# Sheet1.net
KiCad netlist of a schematic drawn in Altium Designer
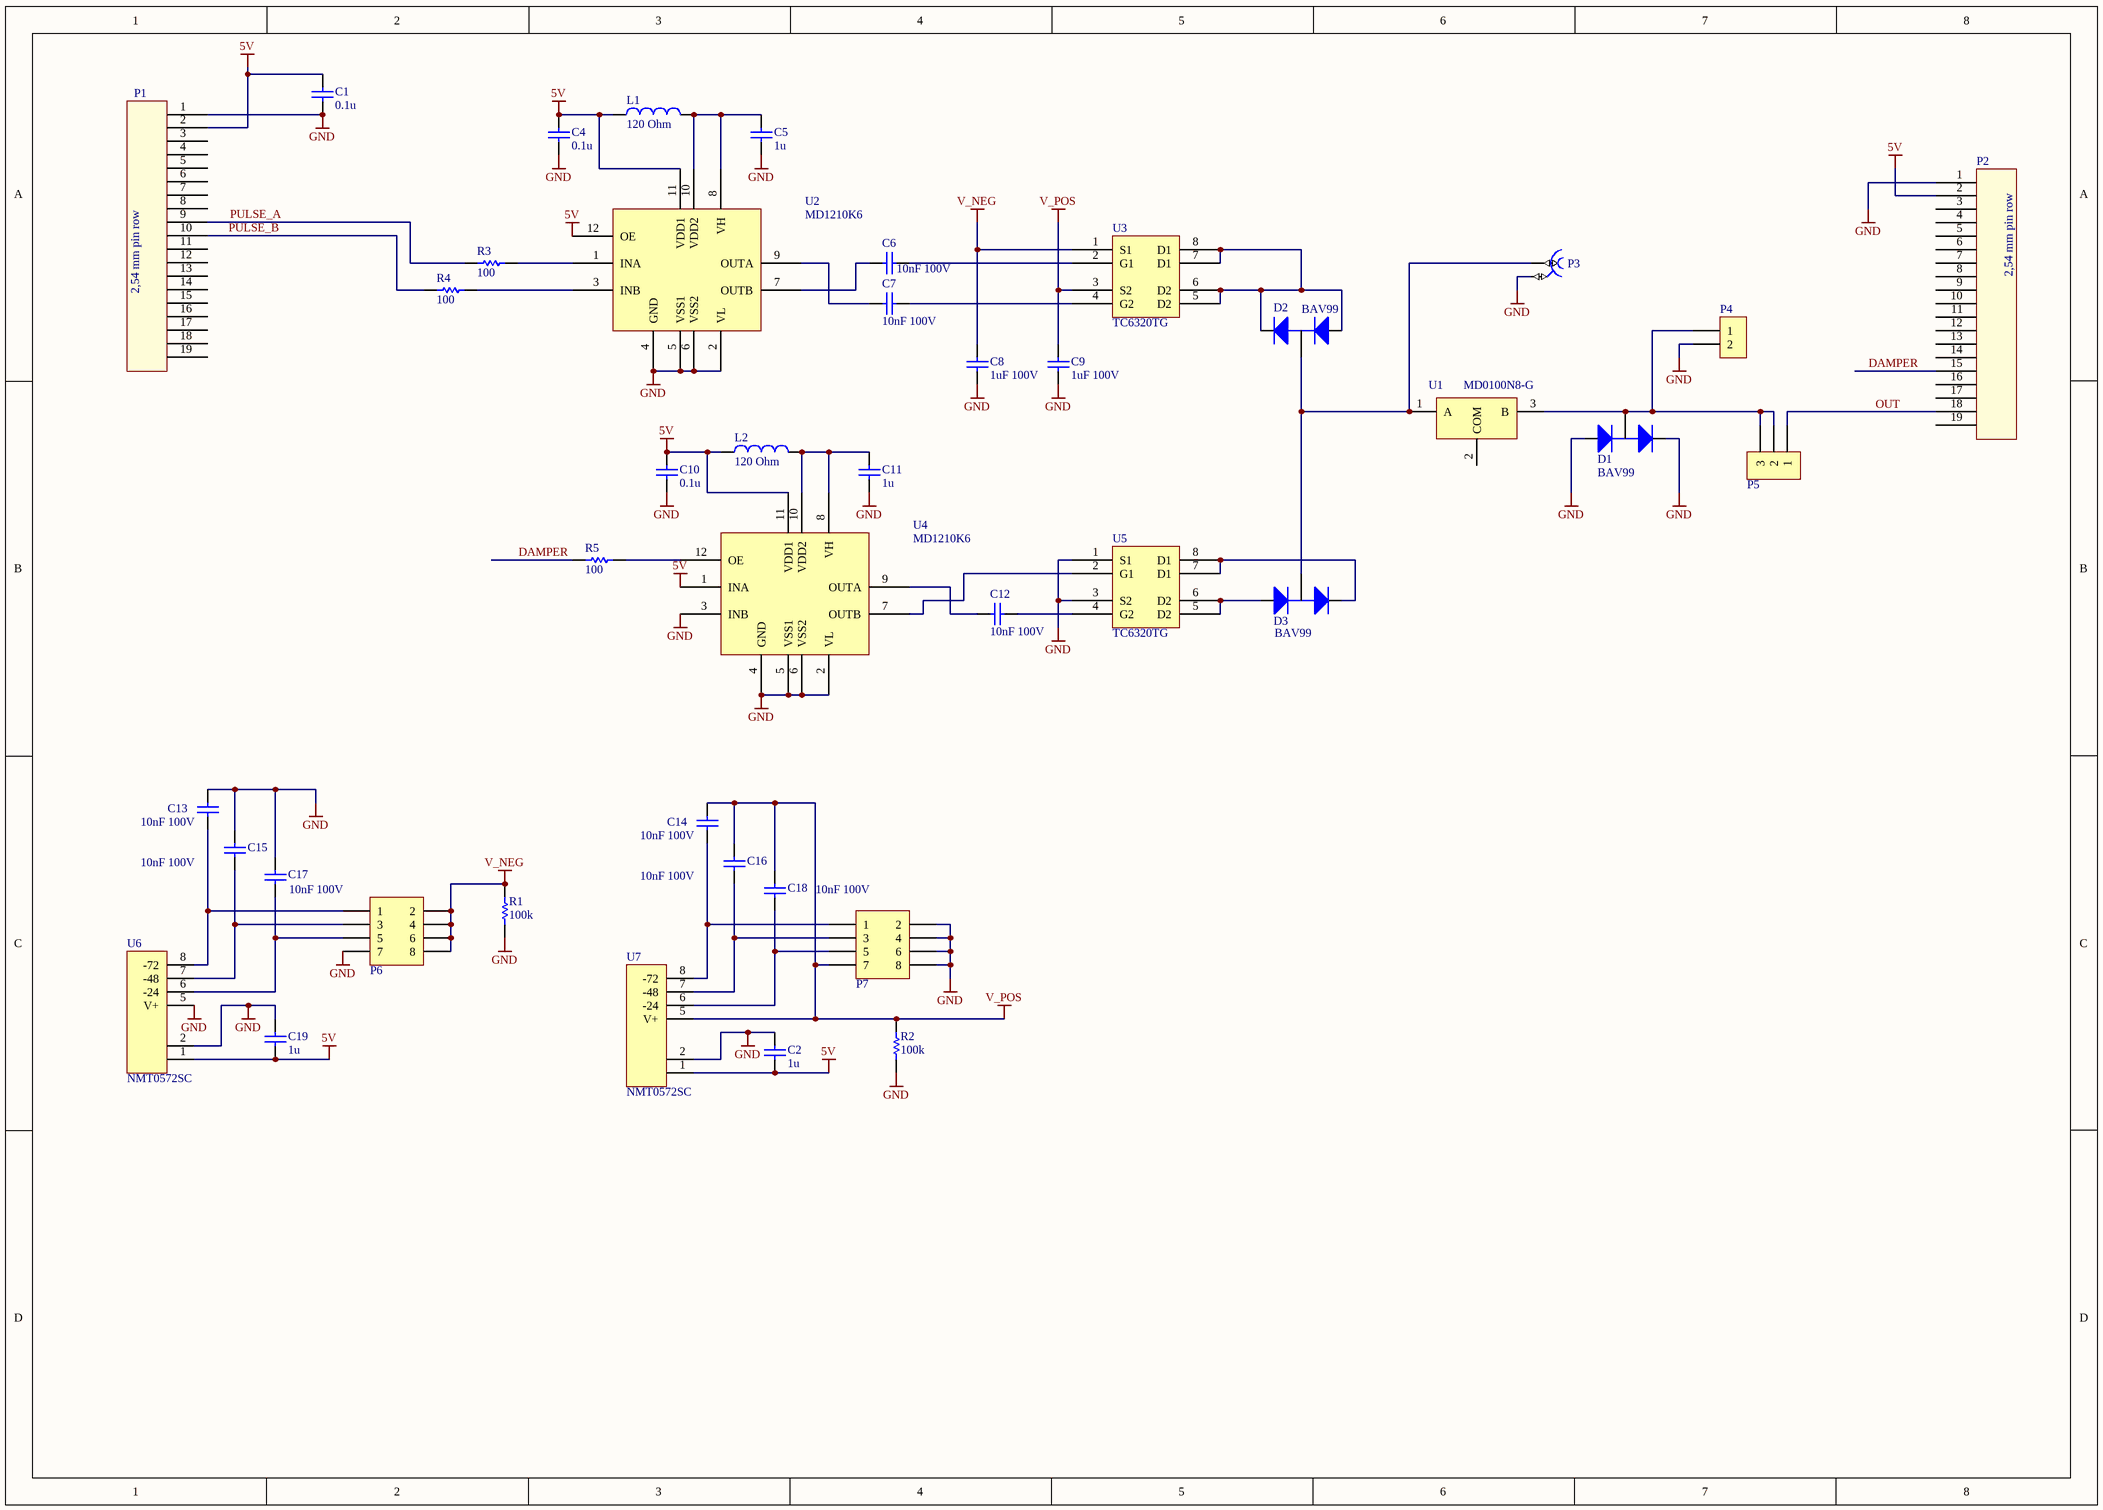
[diagram p0: Sheet1.SchDoc]

(export (version "E")
  (design (tool "Eeschema 10.0.6"))
  (components
    (comp (ref "C1")
      (value "0.1u")
      (footprint "0603RC")
      (description "Capacitor")
      (fields (field (name "PUBLISHER") "Altium Limited"))
      (libsource (lib "Miscellaneous Devices") (part "Cap"))
    )
    (comp (ref "C2")
      (value "1u")
      (footprint "0805RC")
      (description "Capacitor")
      (fields (field (name "PUBLISHER") "Altium Limited"))
      (libsource (lib "Miscellaneous Devices") (part "Cap"))
    )
    (comp (ref "C4")
      (value "0.1u")
      (footprint "0603RC")
      (description "Capacitor")
      (fields (field (name "PUBLISHER") "Altium Limited"))
      (libsource (lib "Miscellaneous Devices") (part "Cap"))
    )
    (comp (ref "C5")
      (value "1u")
      (footprint "0805RC")
      (description "Capacitor")
      (fields (field (name "PUBLISHER") "Altium Limited"))
      (libsource (lib "Miscellaneous Devices") (part "Cap"))
    )
    (comp (ref "C6")
      (value "10nF 100V")
      (footprint "0805RC")
      (description "Capacitor")
      (fields (field (name "PUBLISHER") "Altium Limited"))
      (libsource (lib "Miscellaneous Devices") (part "Cap"))
    )
    (comp (ref "C7")
      (value "10nF 100V")
      (footprint "0805RC")
      (description "Capacitor")
      (fields (field (name "PUBLISHER") "Altium Limited"))
      (libsource (lib "Miscellaneous Devices") (part "Cap"))
    )
    (comp (ref "C8")
      (value "1uF 100V")
      (footprint "1206RC")
      (description "Capacitor")
      (fields (field (name "PUBLISHER") "Altium Limited"))
      (libsource (lib "Miscellaneous Devices") (part "Cap"))
    )
    (comp (ref "C9")
      (value "1uF 100V")
      (footprint "1206RC")
      (description "Capacitor")
      (fields (field (name "PUBLISHER") "Altium Limited"))
      (libsource (lib "Miscellaneous Devices") (part "Cap"))
    )
    (comp (ref "C10")
      (value "0.1u")
      (footprint "0603RC")
      (description "Capacitor")
      (fields (field (name "PUBLISHER") "Altium Limited"))
      (libsource (lib "Miscellaneous Devices") (part "Cap"))
    )
    (comp (ref "C11")
      (value "1u")
      (footprint "0805RC")
      (description "Capacitor")
      (fields (field (name "PUBLISHER") "Altium Limited"))
      (libsource (lib "Miscellaneous Devices") (part "Cap"))
    )
    (comp (ref "C12")
      (value "10nF 100V")
      (footprint "0805RC")
      (description "Capacitor")
      (fields (field (name "PUBLISHER") "Altium Limited"))
      (libsource (lib "Miscellaneous Devices") (part "Cap"))
    )
    (comp (ref "C13")
      (value "10nF 100V")
      (footprint "0805RC")
      (description "Capacitor")
      (fields (field (name "PUBLISHER") "Altium Limited"))
      (libsource (lib "Miscellaneous Devices") (part "Cap"))
    )
    (comp (ref "C14")
      (value "10nF 100V")
      (footprint "0805RC")
      (description "Capacitor")
      (fields (field (name "PUBLISHER") "Altium Limited"))
      (libsource (lib "Miscellaneous Devices") (part "Cap"))
    )
    (comp (ref "C15")
      (value "10nF 100V")
      (footprint "0805RC")
      (description "Capacitor")
      (fields (field (name "PUBLISHER") "Altium Limited"))
      (libsource (lib "Miscellaneous Devices") (part "Cap"))
    )
    (comp (ref "C16")
      (value "10nF 100V")
      (footprint "0805RC")
      (description "Capacitor")
      (fields (field (name "PUBLISHER") "Altium Limited"))
      (libsource (lib "Miscellaneous Devices") (part "Cap"))
    )
    (comp (ref "C17")
      (value "10nF 100V")
      (footprint "0805RC")
      (description "Capacitor")
      (fields (field (name "PUBLISHER") "Altium Limited"))
      (libsource (lib "Miscellaneous Devices") (part "Cap"))
    )
    (comp (ref "C18")
      (value "10nF 100V")
      (footprint "0805RC")
      (description "Capacitor")
      (fields (field (name "PUBLISHER") "Altium Limited"))
      (libsource (lib "Miscellaneous Devices") (part "Cap"))
    )
    (comp (ref "C19")
      (value "1u")
      (footprint "0805RC")
      (description "Capacitor")
      (fields (field (name "PUBLISHER") "Altium Limited"))
      (libsource (lib "Miscellaneous Devices") (part "Cap"))
    )
    (comp (ref "D1")
      (value "BAV99")
      (footprint "SOT-23")
      (description "Medium-speed Switching Double Diode with Low Leakage Current")
      (fields (field (name "PUBLISHER") "Altium Limited"))
      (libsource (lib "Miscellaneous Devices") (part "BAV199"))
    )
    (comp (ref "D2")
      (value "BAV99")
      (footprint "SOT-23")
      (description "Medium-speed Switching Double Diode with Low Leakage Current")
      (fields (field (name "PUBLISHER") "Altium Limited"))
      (libsource (lib "Miscellaneous Devices") (part "BAV199"))
    )
    (comp (ref "D3")
      (value "BAV99")
      (footprint "SOT-23")
      (description "Medium-speed Switching Double Diode with Low Leakage Current")
      (fields (field (name "PUBLISHER") "Altium Limited"))
      (libsource (lib "Miscellaneous Devices") (part "BAV199"))
    )
    (comp (ref "L1")
      (value "120 Ohm")
      (footprint "0805R")
      (description "Inductor")
      (fields (field (name "Comment") "BLM21PG121SN1D") (field (name "PUBLISHER") "Altium Limited"))
      (libsource (lib "Miscellaneous Devices") (part "Inductor"))
    )
    (comp (ref "L2")
      (value "120 Ohm")
      (footprint "0805R")
      (description "Inductor")
      (fields (field (name "Comment") "BLM21PG121SN1D") (field (name "PUBLISHER") "Altium Limited"))
      (libsource (lib "Miscellaneous Devices") (part "Inductor"))
    )
    (comp (ref "P1")
      (value "PLS_2.54mm-19")
      (footprint "PLS_2.54mm-19")
      (libsource (lib "") (part "PLS_2.54mm-19_1"))
    )
    (comp (ref "P2")
      (value "PLS_2.54mm-19")
      (footprint "PLS_2.54mm-19")
      (libsource (lib "alt_vovan") (part "PLS_2.54mm-19"))
    )
    (comp (ref "P3")
      (value "SMA")
      (footprint "echOpen_ADC_Card:AMPHENOL_132357-11")
      (fields
        (field (name "PART NUMBER") "AMPHENOL_132357-11")
        (field (name "MANUFACTURER") "AMPHENOL")
        (field (name "MANUFACTURER PART NUMBER") "132357-11")
        (field (name "AUTHOR") "CERN DEM JLC")
      )
      (libsource (lib "Sof-Connectors") (part "Coax_1Female_1Shield"))
    )
    (comp (ref "P4")
      (value "SCSL-2")
      (footprint "SCSL-2")
      (description "2-pin general header")
      (fields (field (name "PUBLISHER") "Altium Limited"))
      (libsource (lib "Miscellaneous Devices") (part "Header 2"))
    )
    (comp (ref "P5")
      (value "PLS-3")
      (footprint "PLS-3")
      (description "3-pin general header")
      (fields (field (name "PUBLISHER") "Altium Limited"))
      (libsource (lib "Miscellaneous Devices") (part "Header 3"))
    )
    (comp (ref "P6")
      (value "PLD-8")
      (footprint "PLD-8")
      (description "Header, 4-Pin, Dual row")
      (fields (field (name "PUBLISHER") "Altium Limited"))
      (libsource (lib "Miscellaneous Devices") (part "Header 4X2"))
    )
    (comp (ref "P7")
      (value "PLD-8")
      (footprint "PLD-8")
      (description "Header, 4-Pin, Dual row")
      (fields (field (name "PUBLISHER") "Altium Limited"))
      (libsource (lib "Miscellaneous Devices") (part "Header 4X2"))
    )
    (comp (ref "R1")
      (value "100k")
      (footprint "0805R")
      (description "Resistor")
      (fields (field (name "PUBLISHER") "Altium Limited"))
      (libsource (lib "Miscellaneous Devices") (part "Res1"))
    )
    (comp (ref "R2")
      (value "100k")
      (footprint "0805R")
      (description "Resistor")
      (fields (field (name "PUBLISHER") "Altium Limited"))
      (libsource (lib "Miscellaneous Devices") (part "Res1"))
    )
    (comp (ref "R3")
      (value "100")
      (footprint "0603R")
      (description "Resistor")
      (fields (field (name "PUBLISHER") "Altium Limited"))
      (libsource (lib "Miscellaneous Devices") (part "Res1"))
    )
    (comp (ref "R4")
      (value "100")
      (footprint "0603R")
      (description "Resistor")
      (fields (field (name "PUBLISHER") "Altium Limited"))
      (libsource (lib "Miscellaneous Devices") (part "Res1"))
    )
    (comp (ref "R5")
      (value "100")
      (footprint "0603R")
      (description "Resistor")
      (fields (field (name "PUBLISHER") "Altium Limited"))
      (libsource (lib "Miscellaneous Devices") (part "Res1"))
    )
    (comp (ref "U1")
      (value "MD0100N8-G")
      (footprint "echOpen_ADC_Card:SOT89")
      (description "3-Ultra-Sound HV Switch 1=A 2=COM 3=B")
      (fields (field (name "MANUFACTURER") "Supertex inc.") (field (name "AUTHOR") "S. Jafar"))
      (libsource (lib "Sof-ICs And Semiconductors") (part "MD0100"))
    )
    (comp (ref "U2") (value "MD1210K6") (footprint "QFN-12 4x4mm") (libsource (lib "Pulser") (part "MD1210")))
    (comp (ref "U3")
      (value "TC6320TG")
      (footprint "SOIC127P600-8N")
      (description "N- and P-Channel  Enhancement-Mode MOSFET Pair")
      (libsource (lib "Pulser") (part "TC6320"))
    )
    (comp (ref "U4") (value "MD1210K6") (footprint "QFN-12 4x4mm") (libsource (lib "Pulser") (part "MD1210")))
    (comp (ref "U5")
      (value "TC6320TG")
      (footprint "SOIC127P600-8N")
      (description "N- and P-Channel  Enhancement-Mode MOSFET Pair")
      (libsource (lib "Pulser") (part "TC6320"))
    )
    (comp (ref "U6")
      (value "NMT0572SC")
      (footprint "NMT0572SC")
      (description "Horizontal")
      (fields (field (name "PUBLISHER") "Altium Limited"))
      (libsource (lib "Miscellaneous Devices") (part "Header 8"))
    )
    (comp (ref "U7")
      (value "NMT0572SC")
      (footprint "NMT0572SC")
      (description "Horizontal")
      (fields (field (name "PUBLISHER") "Altium Limited"))
      (libsource (lib "Miscellaneous Devices") (part "Header 8"))
    )
  )
  (nets
    (net (code "1") (name "/DAMPER") (class "Default")
      (node (ref "P2") (pin "15") (pinfunction "15_15") (pintype "passive"))
      (node (ref "R5") (pin "1") (pinfunction "1_1") (pintype "passive"))
    )
    (net (code "3") (name "/PULSE_A") (class "Default")
      (node (ref "P1") (pin "9") (pinfunction "9_9") (pintype "passive"))
      (node (ref "R3") (pin "1") (pinfunction "1_1") (pintype "passive"))
    )
    (net (code "4") (name "/PULSE_B") (class "Default")
      (node (ref "P1") (pin "10") (pinfunction "10_10") (pintype "passive"))
      (node (ref "R4") (pin "1") (pinfunction "1_1") (pintype "passive"))
    )
    (net (code "5") (name "5V") (class "Default")
      (node (ref "C1") (pin "2") (pinfunction "2_2") (pintype "passive"))
      (node (ref "C10") (pin "2") (pinfunction "2_2") (pintype "passive"))
      (node (ref "C19") (pin "1") (pinfunction "1_1") (pintype "passive"))
      (node (ref "C2") (pin "1") (pinfunction "1_1") (pintype "passive"))
      (node (ref "C4") (pin "2") (pinfunction "2_2") (pintype "passive"))
      (node (ref "L1") (pin "1") (pinfunction "1_1") (pintype "passive"))
      (node (ref "L2") (pin "1") (pinfunction "1_1") (pintype "passive"))
      (node (ref "P1") (pin "2") (pinfunction "2_2") (pintype "passive"))
      (node (ref "P2") (pin "2") (pinfunction "2_2") (pintype "passive"))
      (node (ref "U2") (pin "11") (pinfunction "VDD1_11") (pintype "passive"))
      (node (ref "U2") (pin "12") (pinfunction "OE_12") (pintype "passive"))
      (node (ref "U4") (pin "1") (pinfunction "INA_1") (pintype "passive"))
      (node (ref "U4") (pin "11") (pinfunction "VDD1_11") (pintype "passive"))
      (node (ref "U6") (pin "1") (pinfunction "1_1") (pintype "passive"))
      (node (ref "U7") (pin "1") (pinfunction "1_1") (pintype "passive"))
    )
    (net (code "6") (name "GND") (class "Default")
      (node (ref "C1") (pin "1") (pinfunction "1_1") (pintype "passive"))
      (node (ref "C10") (pin "1") (pinfunction "1_1") (pintype "passive"))
      (node (ref "C11") (pin "1") (pinfunction "1_1") (pintype "passive"))
      (node (ref "C13") (pin "1") (pinfunction "1_1") (pintype "passive"))
      (node (ref "C15") (pin "1") (pinfunction "1_1") (pintype "passive"))
      (node (ref "C17") (pin "1") (pinfunction "1_1") (pintype "passive"))
      (node (ref "C19") (pin "2") (pinfunction "2_2") (pintype "passive"))
      (node (ref "C2") (pin "2") (pinfunction "2_2") (pintype "passive"))
      (node (ref "C4") (pin "1") (pinfunction "1_1") (pintype "passive"))
      (node (ref "C5") (pin "1") (pinfunction "1_1") (pintype "passive"))
      (node (ref "C8") (pin "1") (pinfunction "1_1") (pintype "passive"))
      (node (ref "C9") (pin "1") (pinfunction "1_1") (pintype "passive"))
      (node (ref "D1") (pin "1") (pinfunction "A_1") (pintype "passive"))
      (node (ref "D1") (pin "2") (pinfunction "K_2") (pintype "passive"))
      (node (ref "P1") (pin "1") (pinfunction "1_1") (pintype "passive"))
      (node (ref "P2") (pin "1") (pinfunction "1_1") (pintype "passive"))
      (node (ref "P3") (pin "2") (pinfunction "2_2") (pintype "bidirectional"))
      (node (ref "P4") (pin "2") (pinfunction "2_2") (pintype "passive"))
      (node (ref "P6") (pin "7") (pinfunction "7_7") (pintype "passive"))
      (node (ref "P7") (pin "2") (pinfunction "2_2") (pintype "passive"))
      (node (ref "P7") (pin "4") (pinfunction "4_4") (pintype "passive"))
      (node (ref "P7") (pin "6") (pinfunction "6_6") (pintype "passive"))
      (node (ref "P7") (pin "8") (pinfunction "8_8") (pintype "passive"))
      (node (ref "R1") (pin "1") (pinfunction "1_1") (pintype "passive"))
      (node (ref "R2") (pin "1") (pinfunction "1_1") (pintype "passive"))
      (node (ref "U2") (pin "2") (pinfunction "VL_2") (pintype "passive"))
      (node (ref "U2") (pin "4") (pinfunction "GND_4") (pintype "passive"))
      (node (ref "U2") (pin "5") (pinfunction "VSS1_5") (pintype "passive"))
      (node (ref "U2") (pin "6") (pinfunction "VSS2_6") (pintype "passive"))
      (node (ref "U4") (pin "2") (pinfunction "VL_2") (pintype "passive"))
      (node (ref "U4") (pin "3") (pinfunction "INB_3") (pintype "passive"))
      (node (ref "U4") (pin "4") (pinfunction "GND_4") (pintype "passive"))
      (node (ref "U4") (pin "5") (pinfunction "VSS1_5") (pintype "passive"))
      (node (ref "U4") (pin "6") (pinfunction "VSS2_6") (pintype "passive"))
      (node (ref "U5") (pin "1") (pinfunction "S1_1") (pintype "passive"))
      (node (ref "U5") (pin "3") (pinfunction "S2_3") (pintype "passive"))
      (node (ref "U6") (pin "2") (pinfunction "2_2") (pintype "passive"))
      (node (ref "U6") (pin "5") (pinfunction "V+_5") (pintype "passive"))
      (node (ref "U7") (pin "2") (pinfunction "2_2") (pintype "passive"))
    )
    (net (code "7") (name "Net-(D1-C)") (class "Default")
      (node (ref "D1") (pin "3") (pinfunction "C_3") (pintype "passive"))
      (node (ref "P4") (pin "1") (pinfunction "1_1") (pintype "passive"))
      (node (ref "P5") (pin "2") (pinfunction "2_2") (pintype "passive"))
      (node (ref "P5") (pin "3") (pinfunction "3_3") (pintype "passive"))
      (node (ref "U1") (pin "3") (pinfunction "B_3") (pintype "passive"))
    )
    (net (code "8") (name "Net-(D2-A)") (class "Default")
      (node (ref "D2") (pin "1") (pinfunction "A_1") (pintype "passive"))
      (node (ref "D2") (pin "2") (pinfunction "K_2") (pintype "passive"))
      (node (ref "U3") (pin "5") (pinfunction "D2_5") (pintype "passive"))
      (node (ref "U3") (pin "6") (pinfunction "D2_6") (pintype "passive"))
      (node (ref "U3") (pin "7") (pinfunction "D1_7") (pintype "passive"))
      (node (ref "U3") (pin "8") (pinfunction "D1_8") (pintype "passive"))
    )
    (net (code "9") (name "Net-(D2-C)") (class "Default")
      (node (ref "D2") (pin "3") (pinfunction "C_3") (pintype "passive"))
      (node (ref "D3") (pin "3") (pinfunction "C_3") (pintype "passive"))
      (node (ref "P3") (pin "1") (pinfunction "1_1") (pintype "bidirectional"))
      (node (ref "U1") (pin "1") (pinfunction "A_1") (pintype "passive"))
    )
    (net (code "10") (name "Net-(D3-A)") (class "Default")
      (node (ref "D3") (pin "1") (pinfunction "A_1") (pintype "passive"))
      (node (ref "U5") (pin "5") (pinfunction "D2_5") (pintype "passive"))
      (node (ref "U5") (pin "6") (pinfunction "D2_6") (pintype "passive"))
    )
    (net (code "11") (name "Net-(D3-K)") (class "Default")
      (node (ref "D3") (pin "2") (pinfunction "K_2") (pintype "passive"))
      (node (ref "U5") (pin "7") (pinfunction "D1_7") (pintype "passive"))
      (node (ref "U5") (pin "8") (pinfunction "D1_8") (pintype "passive"))
    )
    (net (code "12") (name "Net-(P2-Pad18)") (class "Default")
      (node (ref "P2") (pin "18") (pinfunction "18_18") (pintype "passive"))
      (node (ref "P5") (pin "1") (pinfunction "1_1") (pintype "passive"))
    )
    (net (code "13") (name "Net-(U2-INA)") (class "Default")
      (node (ref "R3") (pin "2") (pinfunction "2_2") (pintype "passive"))
      (node (ref "U2") (pin "1") (pinfunction "INA_1") (pintype "passive"))
    )
    (net (code "14") (name "Net-(U2-INB)") (class "Default")
      (node (ref "R4") (pin "2") (pinfunction "2_2") (pintype "passive"))
      (node (ref "U2") (pin "3") (pinfunction "INB_3") (pintype "passive"))
    )
    (net (code "15") (name "Net-(U2-OUTA)") (class "Default")
      (node (ref "C7") (pin "2") (pinfunction "2_2") (pintype "passive"))
      (node (ref "U2") (pin "9") (pinfunction "OUTA_9") (pintype "passive"))
    )
    (net (code "16") (name "Net-(U2-OUTB)") (class "Default")
      (node (ref "C6") (pin "2") (pinfunction "2_2") (pintype "passive"))
      (node (ref "U2") (pin "7") (pinfunction "OUTB_7") (pintype "passive"))
    )
    (net (code "17") (name "Net-(U2-VDD2)") (class "Default")
      (node (ref "C5") (pin "2") (pinfunction "2_2") (pintype "passive"))
      (node (ref "L1") (pin "2") (pinfunction "2_2") (pintype "passive"))
      (node (ref "U2") (pin "10") (pinfunction "VDD2_10") (pintype "passive"))
      (node (ref "U2") (pin "8") (pinfunction "VH_8") (pintype "passive"))
    )
    (net (code "18") (name "Net-(U3-G1)") (class "Default")
      (node (ref "C6") (pin "1") (pinfunction "1_1") (pintype "passive"))
      (node (ref "U3") (pin "2") (pinfunction "G1_2") (pintype "passive"))
    )
    (net (code "19") (name "Net-(U3-G2)") (class "Default")
      (node (ref "C7") (pin "1") (pinfunction "1_1") (pintype "passive"))
      (node (ref "U3") (pin "4") (pinfunction "G2_4") (pintype "passive"))
    )
    (net (code "20") (name "Net-(U4-OE)") (class "Default")
      (node (ref "R5") (pin "2") (pinfunction "2_2") (pintype "passive"))
      (node (ref "U4") (pin "12") (pinfunction "OE_12") (pintype "passive"))
    )
    (net (code "21") (name "Net-(U4-OUTA)") (class "Default")
      (node (ref "C12") (pin "2") (pinfunction "2_2") (pintype "passive"))
      (node (ref "U4") (pin "9") (pinfunction "OUTA_9") (pintype "passive"))
    )
    (net (code "22") (name "Net-(U4-OUTB)") (class "Default")
      (node (ref "U4") (pin "7") (pinfunction "OUTB_7") (pintype "passive"))
      (node (ref "U5") (pin "2") (pinfunction "G1_2") (pintype "passive"))
    )
    (net (code "23") (name "Net-(U4-VDD2)") (class "Default")
      (node (ref "C11") (pin "2") (pinfunction "2_2") (pintype "passive"))
      (node (ref "L2") (pin "2") (pinfunction "2_2") (pintype "passive"))
      (node (ref "U4") (pin "10") (pinfunction "VDD2_10") (pintype "passive"))
      (node (ref "U4") (pin "8") (pinfunction "VH_8") (pintype "passive"))
    )
    (net (code "24") (name "Net-(U5-G2)") (class "Default")
      (node (ref "C12") (pin "1") (pinfunction "1_1") (pintype "passive"))
      (node (ref "U5") (pin "4") (pinfunction "G2_4") (pintype "passive"))
    )
    (net (code "25") (name "Net-(U6--24)") (class "Default")
      (node (ref "C17") (pin "2") (pinfunction "2_2") (pintype "passive"))
      (node (ref "P6") (pin "5") (pinfunction "5_5") (pintype "passive"))
      (node (ref "U6") (pin "6") (pinfunction "-24_6") (pintype "passive"))
    )
    (net (code "26") (name "Net-(U6--48)") (class "Default")
      (node (ref "C15") (pin "2") (pinfunction "2_2") (pintype "passive"))
      (node (ref "P6") (pin "3") (pinfunction "3_3") (pintype "passive"))
      (node (ref "U6") (pin "7") (pinfunction "-48_7") (pintype "passive"))
    )
    (net (code "27") (name "Net-(U6--72)") (class "Default")
      (node (ref "C13") (pin "2") (pinfunction "2_2") (pintype "passive"))
      (node (ref "P6") (pin "1") (pinfunction "1_1") (pintype "passive"))
      (node (ref "U6") (pin "8") (pinfunction "-72_8") (pintype "passive"))
    )
    (net (code "28") (name "Net-(U7--24)") (class "Default")
      (node (ref "C18") (pin "2") (pinfunction "2_2") (pintype "passive"))
      (node (ref "P7") (pin "5") (pinfunction "5_5") (pintype "passive"))
      (node (ref "U7") (pin "6") (pinfunction "-24_6") (pintype "passive"))
    )
    (net (code "29") (name "Net-(U7--48)") (class "Default")
      (node (ref "C16") (pin "2") (pinfunction "2_2") (pintype "passive"))
      (node (ref "P7") (pin "3") (pinfunction "3_3") (pintype "passive"))
      (node (ref "U7") (pin "7") (pinfunction "-48_7") (pintype "passive"))
    )
    (net (code "30") (name "Net-(U7--72)") (class "Default")
      (node (ref "C14") (pin "2") (pinfunction "2_2") (pintype "passive"))
      (node (ref "P7") (pin "1") (pinfunction "1_1") (pintype "passive"))
      (node (ref "U7") (pin "8") (pinfunction "-72_8") (pintype "passive"))
    )
    (net (code "31") (name "V_NEG") (class "Default")
      (node (ref "C8") (pin "2") (pinfunction "2_2") (pintype "passive"))
      (node (ref "P6") (pin "2") (pinfunction "2_2") (pintype "passive"))
      (node (ref "P6") (pin "4") (pinfunction "4_4") (pintype "passive"))
      (node (ref "P6") (pin "6") (pinfunction "6_6") (pintype "passive"))
      (node (ref "P6") (pin "8") (pinfunction "8_8") (pintype "passive"))
      (node (ref "R1") (pin "2") (pinfunction "2_2") (pintype "passive"))
      (node (ref "U3") (pin "1") (pinfunction "S1_1") (pintype "passive"))
    )
    (net (code "32") (name "V_POS") (class "Default")
      (node (ref "C14") (pin "1") (pinfunction "1_1") (pintype "passive"))
      (node (ref "C16") (pin "1") (pinfunction "1_1") (pintype "passive"))
      (node (ref "C18") (pin "1") (pinfunction "1_1") (pintype "passive"))
      (node (ref "C9") (pin "2") (pinfunction "2_2") (pintype "passive"))
      (node (ref "P7") (pin "7") (pinfunction "7_7") (pintype "passive"))
      (node (ref "R2") (pin "2") (pinfunction "2_2") (pintype "passive"))
      (node (ref "U3") (pin "3") (pinfunction "S2_3") (pintype "passive"))
      (node (ref "U7") (pin "5") (pinfunction "V+_5") (pintype "passive"))
    )
    (net (code "33") (name "unconnected-(P1-Pad3)") (class "Default")
      (node (ref "P1") (pin "3") (pinfunction "3_3") (pintype "passive"))
    )
    (net (code "34") (name "unconnected-(P1-Pad4)") (class "Default")
      (node (ref "P1") (pin "4") (pinfunction "4_4") (pintype "passive"))
    )
    (net (code "35") (name "unconnected-(P1-Pad5)") (class "Default")
      (node (ref "P1") (pin "5") (pinfunction "5_5") (pintype "passive"))
    )
    (net (code "36") (name "unconnected-(P1-Pad6)") (class "Default")
      (node (ref "P1") (pin "6") (pinfunction "6_6") (pintype "passive"))
    )
    (net (code "37") (name "unconnected-(P1-Pad7)") (class "Default")
      (node (ref "P1") (pin "7") (pinfunction "7_7") (pintype "passive"))
    )
    (net (code "38") (name "unconnected-(P1-Pad8)") (class "Default")
      (node (ref "P1") (pin "8") (pinfunction "8_8") (pintype "passive"))
    )
    (net (code "39") (name "unconnected-(P1-Pad11)") (class "Default")
      (node (ref "P1") (pin "11") (pinfunction "11_11") (pintype "passive"))
    )
    (net (code "40") (name "unconnected-(P1-Pad12)") (class "Default")
      (node (ref "P1") (pin "12") (pinfunction "12_12") (pintype "passive"))
    )
    (net (code "41") (name "unconnected-(P1-Pad13)") (class "Default")
      (node (ref "P1") (pin "13") (pinfunction "13_13") (pintype "passive"))
    )
    (net (code "42") (name "unconnected-(P1-Pad14)") (class "Default")
      (node (ref "P1") (pin "14") (pinfunction "14_14") (pintype "passive"))
    )
    (net (code "43") (name "unconnected-(P1-Pad15)") (class "Default")
      (node (ref "P1") (pin "15") (pinfunction "15_15") (pintype "passive"))
    )
    (net (code "44") (name "unconnected-(P1-Pad16)") (class "Default")
      (node (ref "P1") (pin "16") (pinfunction "16_16") (pintype "passive"))
    )
    (net (code "45") (name "unconnected-(P1-Pad17)") (class "Default")
      (node (ref "P1") (pin "17") (pinfunction "17_17") (pintype "passive"))
    )
    (net (code "46") (name "unconnected-(P1-Pad18)") (class "Default")
      (node (ref "P1") (pin "18") (pinfunction "18_18") (pintype "passive"))
    )
    (net (code "47") (name "unconnected-(P1-Pad19)") (class "Default")
      (node (ref "P1") (pin "19") (pinfunction "19_19") (pintype "passive"))
    )
    (net (code "48") (name "unconnected-(P2-Pad3)") (class "Default")
      (node (ref "P2") (pin "3") (pinfunction "3_3") (pintype "passive"))
    )
    (net (code "49") (name "unconnected-(P2-Pad4)") (class "Default")
      (node (ref "P2") (pin "4") (pinfunction "4_4") (pintype "passive"))
    )
    (net (code "50") (name "unconnected-(P2-Pad5)") (class "Default")
      (node (ref "P2") (pin "5") (pinfunction "5_5") (pintype "passive"))
    )
    (net (code "51") (name "unconnected-(P2-Pad6)") (class "Default")
      (node (ref "P2") (pin "6") (pinfunction "6_6") (pintype "passive"))
    )
    (net (code "52") (name "unconnected-(P2-Pad7)") (class "Default")
      (node (ref "P2") (pin "7") (pinfunction "7_7") (pintype "passive"))
    )
    (net (code "53") (name "unconnected-(P2-Pad8)") (class "Default")
      (node (ref "P2") (pin "8") (pinfunction "8_8") (pintype "passive"))
    )
    (net (code "54") (name "unconnected-(P2-Pad9)") (class "Default")
      (node (ref "P2") (pin "9") (pinfunction "9_9") (pintype "passive"))
    )
    (net (code "55") (name "unconnected-(P2-Pad10)") (class "Default")
      (node (ref "P2") (pin "10") (pinfunction "10_10") (pintype "passive"))
    )
    (net (code "56") (name "unconnected-(P2-Pad11)") (class "Default")
      (node (ref "P2") (pin "11") (pinfunction "11_11") (pintype "passive"))
    )
    (net (code "57") (name "unconnected-(P2-Pad12)") (class "Default")
      (node (ref "P2") (pin "12") (pinfunction "12_12") (pintype "passive"))
    )
    (net (code "58") (name "unconnected-(P2-Pad13)") (class "Default")
      (node (ref "P2") (pin "13") (pinfunction "13_13") (pintype "passive"))
    )
    (net (code "59") (name "unconnected-(P2-Pad14)") (class "Default")
      (node (ref "P2") (pin "14") (pinfunction "14_14") (pintype "passive"))
    )
    (net (code "60") (name "unconnected-(P2-Pad16)") (class "Default")
      (node (ref "P2") (pin "16") (pinfunction "16_16") (pintype "passive"))
    )
    (net (code "61") (name "unconnected-(P2-Pad17)") (class "Default")
      (node (ref "P2") (pin "17") (pinfunction "17_17") (pintype "passive"))
    )
    (net (code "62") (name "unconnected-(P2-Pad19)") (class "Default")
      (node (ref "P2") (pin "19") (pinfunction "19_19") (pintype "passive"))
    )
    (net (code "63") (name "unconnected-(U1-COM-Pad2)") (class "Default")
      (node (ref "U1") (pin "2") (pinfunction "COM_2") (pintype "passive"))
    )
    (net (code "64") (name "unconnected-(U6-Pad3)") (class "Default")
      (node (ref "U6") (pin "3") (pinfunction "3_3") (pintype "passive"))
    )
    (net (code "65") (name "unconnected-(U6-Pad4)") (class "Default")
      (node (ref "U6") (pin "4") (pinfunction "4_4") (pintype "passive"))
    )
    (net (code "66") (name "unconnected-(U7-Pad3)") (class "Default")
      (node (ref "U7") (pin "3") (pinfunction "3_3") (pintype "passive"))
    )
    (net (code "67") (name "unconnected-(U7-Pad4)") (class "Default")
      (node (ref "U7") (pin "4") (pinfunction "4_4") (pintype "passive"))
    )
  )
)
